# Convertidor32Lineas.net
KiCad netlist of a schematic drawn in EAGLE
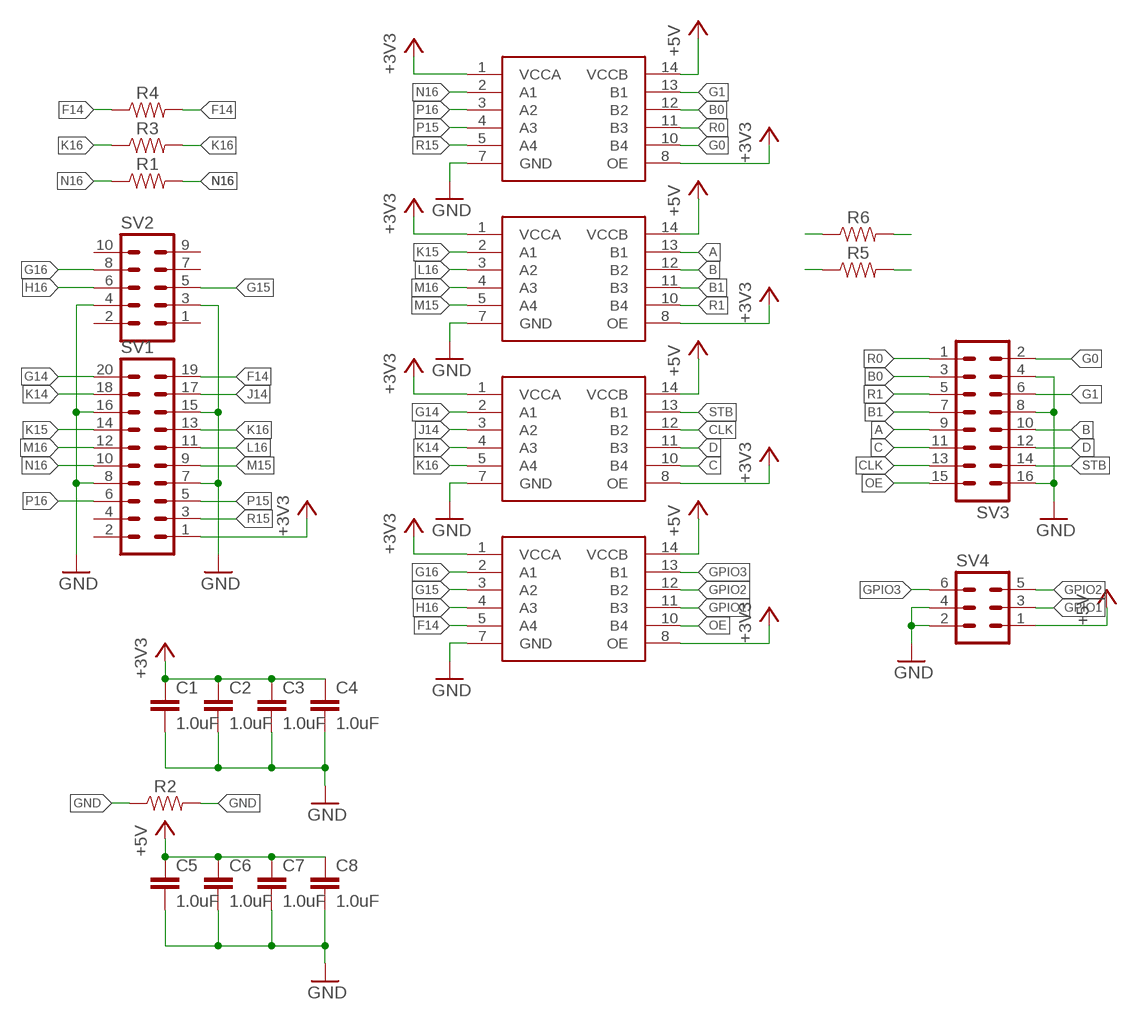
[diagram p0: schematic, sheet 1]

(export (version "E")
  (design (tool "Eeschema 10.0.6"))
  (components
    (comp (ref "C1")
      (value "1.0uF")
      (footprint "eagle-import:0805")
      (libsource (lib "eagle-import") (part "1.0UF-0805-25V-(+80/-20%)"))
    )
    (comp (ref "C2")
      (value "1.0uF")
      (footprint "eagle-import:0805")
      (libsource (lib "eagle-import") (part "1.0UF-0805-25V-(+80/-20%)"))
    )
    (comp (ref "C3")
      (value "1.0uF")
      (footprint "eagle-import:0805")
      (libsource (lib "eagle-import") (part "1.0UF-0805-25V-(+80/-20%)"))
    )
    (comp (ref "C4")
      (value "1.0uF")
      (footprint "eagle-import:0805")
      (libsource (lib "eagle-import") (part "1.0UF-0805-25V-(+80/-20%)"))
    )
    (comp (ref "C5")
      (value "1.0uF")
      (footprint "eagle-import:0805")
      (libsource (lib "eagle-import") (part "1.0UF-0805-25V-(+80/-20%)"))
    )
    (comp (ref "C6")
      (value "1.0uF")
      (footprint "eagle-import:0805")
      (libsource (lib "eagle-import") (part "1.0UF-0805-25V-(+80/-20%)"))
    )
    (comp (ref "C7")
      (value "1.0uF")
      (footprint "eagle-import:0805")
      (libsource (lib "eagle-import") (part "1.0UF-0805-25V-(+80/-20%)"))
    )
    (comp (ref "C8")
      (value "1.0uF")
      (footprint "eagle-import:0805")
      (libsource (lib "eagle-import") (part "1.0UF-0805-25V-(+80/-20%)"))
    )
    (comp (ref "IC1")
      (value "TXB0104")
      (footprint "eagle-import:SO14")
      (libsource (lib "eagle-import") (part "TXB0104"))
    )
    (comp (ref "IC2")
      (value "TXB0104")
      (footprint "eagle-import:SO14")
      (libsource (lib "eagle-import") (part "TXB0104"))
    )
    (comp (ref "IC3")
      (value "TXB0104")
      (footprint "eagle-import:SO14")
      (libsource (lib "eagle-import") (part "TXB0104"))
    )
    (comp (ref "IC4")
      (value "TXB0104")
      (footprint "eagle-import:SO14")
      (libsource (lib "eagle-import") (part "TXB0104"))
    )
    (comp (ref "R1")
      (value "RESISTOR0805")
      (footprint "eagle-import:0805")
      (libsource (lib "eagle-import") (part "RESISTOR0805"))
    )
    (comp (ref "R2")
      (value "RESISTOR0805")
      (footprint "eagle-import:0805")
      (libsource (lib "eagle-import") (part "RESISTOR0805"))
    )
    (comp (ref "R3")
      (value "RESISTOR0805")
      (footprint "eagle-import:0805")
      (libsource (lib "eagle-import") (part "RESISTOR0805"))
    )
    (comp (ref "R4")
      (value "RESISTOR0805")
      (footprint "eagle-import:0805")
      (libsource (lib "eagle-import") (part "RESISTOR0805"))
    )
    (comp (ref "R5")
      (value "RESISTOR0805")
      (footprint "eagle-import:0805")
      (libsource (lib "eagle-import") (part "RESISTOR0805"))
    )
    (comp (ref "R6")
      (value "RESISTOR0805")
      (footprint "eagle-import:0805")
      (libsource (lib "eagle-import") (part "RESISTOR0805"))
    )
    (comp (ref "SV1")
      (value "MA10-2")
      (footprint "eagle-import:MA10-2")
      (libsource (lib "eagle-import") (part "MA10-2"))
    )
    (comp (ref "SV2")
      (value "MA05-2")
      (footprint "eagle-import:MA05-2")
      (libsource (lib "eagle-import") (part "MA05-2"))
    )
    (comp (ref "SV3")
      (value "MA08-2")
      (footprint "eagle-import:MA08-2")
      (libsource (lib "eagle-import") (part "MA08-2"))
    )
    (comp (ref "SV4")
      (value "MA03-2")
      (footprint "eagle-import:MA03-2")
      (libsource (lib "eagle-import") (part "MA03-2"))
    )
  )
  (nets
    (net (code "1") (name "+3V3") (class "Default")
      (node (ref "C1") (pin "1") (pinfunction "1_1") (pintype "passive"))
      (node (ref "C2") (pin "1") (pinfunction "1_1") (pintype "passive"))
      (node (ref "C3") (pin "1") (pinfunction "1_1") (pintype "passive"))
      (node (ref "C4") (pin "1") (pinfunction "1_1") (pintype "passive"))
      (node (ref "IC1") (pin "1") (pinfunction "VCCA_1") (pintype "power_in"))
      (node (ref "IC1") (pin "8") (pinfunction "OE_8") (pintype "input"))
      (node (ref "IC2") (pin "1") (pinfunction "VCCA_1") (pintype "power_in"))
      (node (ref "IC2") (pin "8") (pinfunction "OE_8") (pintype "input"))
      (node (ref "IC3") (pin "1") (pinfunction "VCCA_1") (pintype "power_in"))
      (node (ref "IC3") (pin "8") (pinfunction "OE_8") (pintype "input"))
      (node (ref "IC4") (pin "1") (pinfunction "VCCA_1") (pintype "power_in"))
      (node (ref "IC4") (pin "8") (pinfunction "OE_8") (pintype "input"))
      (node (ref "SV1") (pin "1") (pinfunction "1_1") (pintype "passive"))
    )
    (net (code "2") (name "+5V") (class "Default")
      (node (ref "C5") (pin "1") (pinfunction "1_1") (pintype "passive"))
      (node (ref "C6") (pin "1") (pinfunction "1_1") (pintype "passive"))
      (node (ref "C7") (pin "1") (pinfunction "1_1") (pintype "passive"))
      (node (ref "C8") (pin "1") (pinfunction "1_1") (pintype "passive"))
      (node (ref "IC1") (pin "14") (pinfunction "VCCB_14") (pintype "power_in"))
      (node (ref "IC2") (pin "14") (pinfunction "VCCB_14") (pintype "power_in"))
      (node (ref "IC3") (pin "14") (pinfunction "VCCB_14") (pintype "power_in"))
      (node (ref "IC4") (pin "14") (pinfunction "VCCB_14") (pintype "power_in"))
      (node (ref "SV4") (pin "1") (pinfunction "1_1") (pintype "passive"))
    )
    (net (code "3") (name "A") (class "Default")
      (node (ref "IC2") (pin "13") (pinfunction "B1_13") (pintype "bidirectional"))
      (node (ref "SV3") (pin "9") (pinfunction "9_9") (pintype "passive"))
    )
    (net (code "4") (name "B") (class "Default")
      (node (ref "IC2") (pin "12") (pinfunction "B2_12") (pintype "bidirectional"))
      (node (ref "SV3") (pin "10") (pinfunction "10_10") (pintype "passive"))
    )
    (net (code "5") (name "B0") (class "Default")
      (node (ref "IC1") (pin "12") (pinfunction "B2_12") (pintype "bidirectional"))
      (node (ref "SV3") (pin "3") (pinfunction "3_3") (pintype "passive"))
    )
    (net (code "6") (name "B1") (class "Default")
      (node (ref "IC2") (pin "11") (pinfunction "B3_11") (pintype "bidirectional"))
      (node (ref "SV3") (pin "7") (pinfunction "7_7") (pintype "passive"))
    )
    (net (code "7") (name "C") (class "Default")
      (node (ref "IC3") (pin "10") (pinfunction "B4_10") (pintype "bidirectional"))
      (node (ref "SV3") (pin "11") (pinfunction "11_11") (pintype "passive"))
    )
    (net (code "8") (name "CLK") (class "Default")
      (node (ref "IC3") (pin "12") (pinfunction "B2_12") (pintype "bidirectional"))
      (node (ref "SV3") (pin "13") (pinfunction "13_13") (pintype "passive"))
    )
    (net (code "9") (name "D") (class "Default")
      (node (ref "IC3") (pin "11") (pinfunction "B3_11") (pintype "bidirectional"))
      (node (ref "SV3") (pin "12") (pinfunction "12_12") (pintype "passive"))
    )
    (net (code "10") (name "F14") (class "Default")
      (node (ref "IC4") (pin "5") (pinfunction "A4_5") (pintype "bidirectional"))
      (node (ref "R4") (pin "1") (pinfunction "1_1") (pintype "passive"))
      (node (ref "R4") (pin "2") (pinfunction "2_2") (pintype "passive"))
      (node (ref "SV1") (pin "19") (pinfunction "19_19") (pintype "passive"))
    )
    (net (code "11") (name "G0") (class "Default")
      (node (ref "IC1") (pin "10") (pinfunction "B4_10") (pintype "bidirectional"))
      (node (ref "SV3") (pin "2") (pinfunction "2_2") (pintype "passive"))
    )
    (net (code "12") (name "G1") (class "Default")
      (node (ref "IC1") (pin "13") (pinfunction "B1_13") (pintype "bidirectional"))
      (node (ref "SV3") (pin "6") (pinfunction "6_6") (pintype "passive"))
    )
    (net (code "13") (name "G14") (class "Default")
      (node (ref "IC3") (pin "2") (pinfunction "A1_2") (pintype "bidirectional"))
      (node (ref "SV1") (pin "20") (pinfunction "20_20") (pintype "passive"))
    )
    (net (code "14") (name "G15") (class "Default")
      (node (ref "IC4") (pin "3") (pinfunction "A2_3") (pintype "bidirectional"))
      (node (ref "SV2") (pin "5") (pinfunction "5_5") (pintype "passive"))
    )
    (net (code "15") (name "G16") (class "Default")
      (node (ref "IC4") (pin "2") (pinfunction "A1_2") (pintype "bidirectional"))
      (node (ref "SV2") (pin "8") (pinfunction "8_8") (pintype "passive"))
    )
    (net (code "16") (name "GND") (class "Default")
      (node (ref "C1") (pin "2") (pinfunction "2_2") (pintype "passive"))
      (node (ref "C2") (pin "2") (pinfunction "2_2") (pintype "passive"))
      (node (ref "C3") (pin "2") (pinfunction "2_2") (pintype "passive"))
      (node (ref "C4") (pin "2") (pinfunction "2_2") (pintype "passive"))
      (node (ref "C5") (pin "2") (pinfunction "2_2") (pintype "passive"))
      (node (ref "C6") (pin "2") (pinfunction "2_2") (pintype "passive"))
      (node (ref "C7") (pin "2") (pinfunction "2_2") (pintype "passive"))
      (node (ref "C8") (pin "2") (pinfunction "2_2") (pintype "passive"))
      (node (ref "IC1") (pin "7") (pinfunction "GND_7") (pintype "power_in"))
      (node (ref "IC2") (pin "7") (pinfunction "GND_7") (pintype "power_in"))
      (node (ref "IC3") (pin "7") (pinfunction "GND_7") (pintype "power_in"))
      (node (ref "IC4") (pin "7") (pinfunction "GND_7") (pintype "power_in"))
      (node (ref "R2") (pin "1") (pinfunction "1_1") (pintype "passive"))
      (node (ref "R2") (pin "2") (pinfunction "2_2") (pintype "passive"))
      (node (ref "SV1") (pin "15") (pinfunction "15_15") (pintype "passive"))
      (node (ref "SV1") (pin "16") (pinfunction "16_16") (pintype "passive"))
      (node (ref "SV1") (pin "7") (pinfunction "7_7") (pintype "passive"))
      (node (ref "SV1") (pin "8") (pinfunction "8_8") (pintype "passive"))
      (node (ref "SV2") (pin "3") (pinfunction "3_3") (pintype "passive"))
      (node (ref "SV2") (pin "4") (pinfunction "4_4") (pintype "passive"))
      (node (ref "SV3") (pin "16") (pinfunction "16_16") (pintype "passive"))
      (node (ref "SV3") (pin "4") (pinfunction "4_4") (pintype "passive"))
      (node (ref "SV3") (pin "8") (pinfunction "8_8") (pintype "passive"))
      (node (ref "SV4") (pin "2") (pinfunction "2_2") (pintype "passive"))
      (node (ref "SV4") (pin "4") (pinfunction "4_4") (pintype "passive"))
    )
    (net (code "17") (name "GPIO1") (class "Default")
      (node (ref "IC4") (pin "11") (pinfunction "B3_11") (pintype "bidirectional"))
      (node (ref "SV4") (pin "3") (pinfunction "3_3") (pintype "passive"))
    )
    (net (code "18") (name "GPIO2") (class "Default")
      (node (ref "IC4") (pin "12") (pinfunction "B2_12") (pintype "bidirectional"))
      (node (ref "SV4") (pin "5") (pinfunction "5_5") (pintype "passive"))
    )
    (net (code "19") (name "GPIO3") (class "Default")
      (node (ref "IC4") (pin "13") (pinfunction "B1_13") (pintype "bidirectional"))
      (node (ref "SV4") (pin "6") (pinfunction "6_6") (pintype "passive"))
    )
    (net (code "20") (name "H16") (class "Default")
      (node (ref "IC4") (pin "4") (pinfunction "A3_4") (pintype "bidirectional"))
      (node (ref "SV2") (pin "6") (pinfunction "6_6") (pintype "passive"))
    )
    (net (code "21") (name "J14") (class "Default")
      (node (ref "IC3") (pin "3") (pinfunction "A2_3") (pintype "bidirectional"))
      (node (ref "SV1") (pin "17") (pinfunction "17_17") (pintype "passive"))
    )
    (net (code "22") (name "K14") (class "Default")
      (node (ref "IC3") (pin "4") (pinfunction "A3_4") (pintype "bidirectional"))
      (node (ref "SV1") (pin "18") (pinfunction "18_18") (pintype "passive"))
    )
    (net (code "23") (name "K15") (class "Default")
      (node (ref "IC2") (pin "2") (pinfunction "A1_2") (pintype "bidirectional"))
      (node (ref "SV1") (pin "14") (pinfunction "14_14") (pintype "passive"))
    )
    (net (code "24") (name "K16") (class "Default")
      (node (ref "IC3") (pin "5") (pinfunction "A4_5") (pintype "bidirectional"))
      (node (ref "R3") (pin "1") (pinfunction "1_1") (pintype "passive"))
      (node (ref "R3") (pin "2") (pinfunction "2_2") (pintype "passive"))
      (node (ref "SV1") (pin "13") (pinfunction "13_13") (pintype "passive"))
    )
    (net (code "25") (name "L16") (class "Default")
      (node (ref "IC2") (pin "3") (pinfunction "A2_3") (pintype "bidirectional"))
      (node (ref "SV1") (pin "11") (pinfunction "11_11") (pintype "passive"))
    )
    (net (code "26") (name "M15") (class "Default")
      (node (ref "IC2") (pin "5") (pinfunction "A4_5") (pintype "bidirectional"))
      (node (ref "SV1") (pin "9") (pinfunction "9_9") (pintype "passive"))
    )
    (net (code "27") (name "M16") (class "Default")
      (node (ref "IC2") (pin "4") (pinfunction "A3_4") (pintype "bidirectional"))
      (node (ref "SV1") (pin "12") (pinfunction "12_12") (pintype "passive"))
    )
    (net (code "28") (name "N16") (class "Default")
      (node (ref "IC1") (pin "2") (pinfunction "A1_2") (pintype "bidirectional"))
      (node (ref "R1") (pin "1") (pinfunction "1_1") (pintype "passive"))
      (node (ref "R1") (pin "2") (pinfunction "2_2") (pintype "passive"))
      (node (ref "SV1") (pin "10") (pinfunction "10_10") (pintype "passive"))
    )
    (net (code "29") (name "OE") (class "Default")
      (node (ref "IC4") (pin "10") (pinfunction "B4_10") (pintype "bidirectional"))
      (node (ref "R6") (pin "1") (pinfunction "1_1") (pintype "passive"))
      (node (ref "R6") (pin "2") (pinfunction "2_2") (pintype "passive"))
      (node (ref "SV3") (pin "15") (pinfunction "15_15") (pintype "passive"))
    )
    (net (code "30") (name "P15") (class "Default")
      (node (ref "IC1") (pin "4") (pinfunction "A3_4") (pintype "bidirectional"))
      (node (ref "SV1") (pin "5") (pinfunction "5_5") (pintype "passive"))
    )
    (net (code "31") (name "P16") (class "Default")
      (node (ref "IC1") (pin "3") (pinfunction "A2_3") (pintype "bidirectional"))
      (node (ref "SV1") (pin "6") (pinfunction "6_6") (pintype "passive"))
    )
    (net (code "32") (name "R0") (class "Default")
      (node (ref "IC1") (pin "11") (pinfunction "B3_11") (pintype "bidirectional"))
      (node (ref "SV3") (pin "1") (pinfunction "1_1") (pintype "passive"))
    )
    (net (code "33") (name "R1") (class "Default")
      (node (ref "IC2") (pin "10") (pinfunction "B4_10") (pintype "bidirectional"))
      (node (ref "R5") (pin "1") (pinfunction "1_1") (pintype "passive"))
      (node (ref "R5") (pin "2") (pinfunction "2_2") (pintype "passive"))
      (node (ref "SV3") (pin "5") (pinfunction "5_5") (pintype "passive"))
    )
    (net (code "34") (name "R15") (class "Default")
      (node (ref "IC1") (pin "5") (pinfunction "A4_5") (pintype "bidirectional"))
      (node (ref "SV1") (pin "3") (pinfunction "3_3") (pintype "passive"))
    )
    (net (code "35") (name "STB") (class "Default")
      (node (ref "IC3") (pin "13") (pinfunction "B1_13") (pintype "bidirectional"))
      (node (ref "SV3") (pin "14") (pinfunction "14_14") (pintype "passive"))
    )
    (net (code "36") (name "unconnected-(SV1-Pad2)") (class "Default")
      (node (ref "SV1") (pin "2") (pinfunction "2_2") (pintype "passive"))
    )
    (net (code "37") (name "unconnected-(SV1-Pad4)") (class "Default")
      (node (ref "SV1") (pin "4") (pinfunction "4_4") (pintype "passive"))
    )
    (net (code "38") (name "unconnected-(SV2-Pad1)") (class "Default")
      (node (ref "SV2") (pin "1") (pinfunction "1_1") (pintype "passive"))
    )
    (net (code "39") (name "unconnected-(SV2-Pad2)") (class "Default")
      (node (ref "SV2") (pin "2") (pinfunction "2_2") (pintype "passive"))
    )
    (net (code "40") (name "unconnected-(SV2-Pad7)") (class "Default")
      (node (ref "SV2") (pin "7") (pinfunction "7_7") (pintype "passive"))
    )
    (net (code "41") (name "unconnected-(SV2-Pad9)") (class "Default")
      (node (ref "SV2") (pin "9") (pinfunction "9_9") (pintype "passive"))
    )
    (net (code "42") (name "unconnected-(SV2-Pad10)") (class "Default")
      (node (ref "SV2") (pin "10") (pinfunction "10_10") (pintype "passive"))
    )
  )
)
